# ArduinoRadioV3.net
KiCad netlist of a schematic drawn in EAGLE
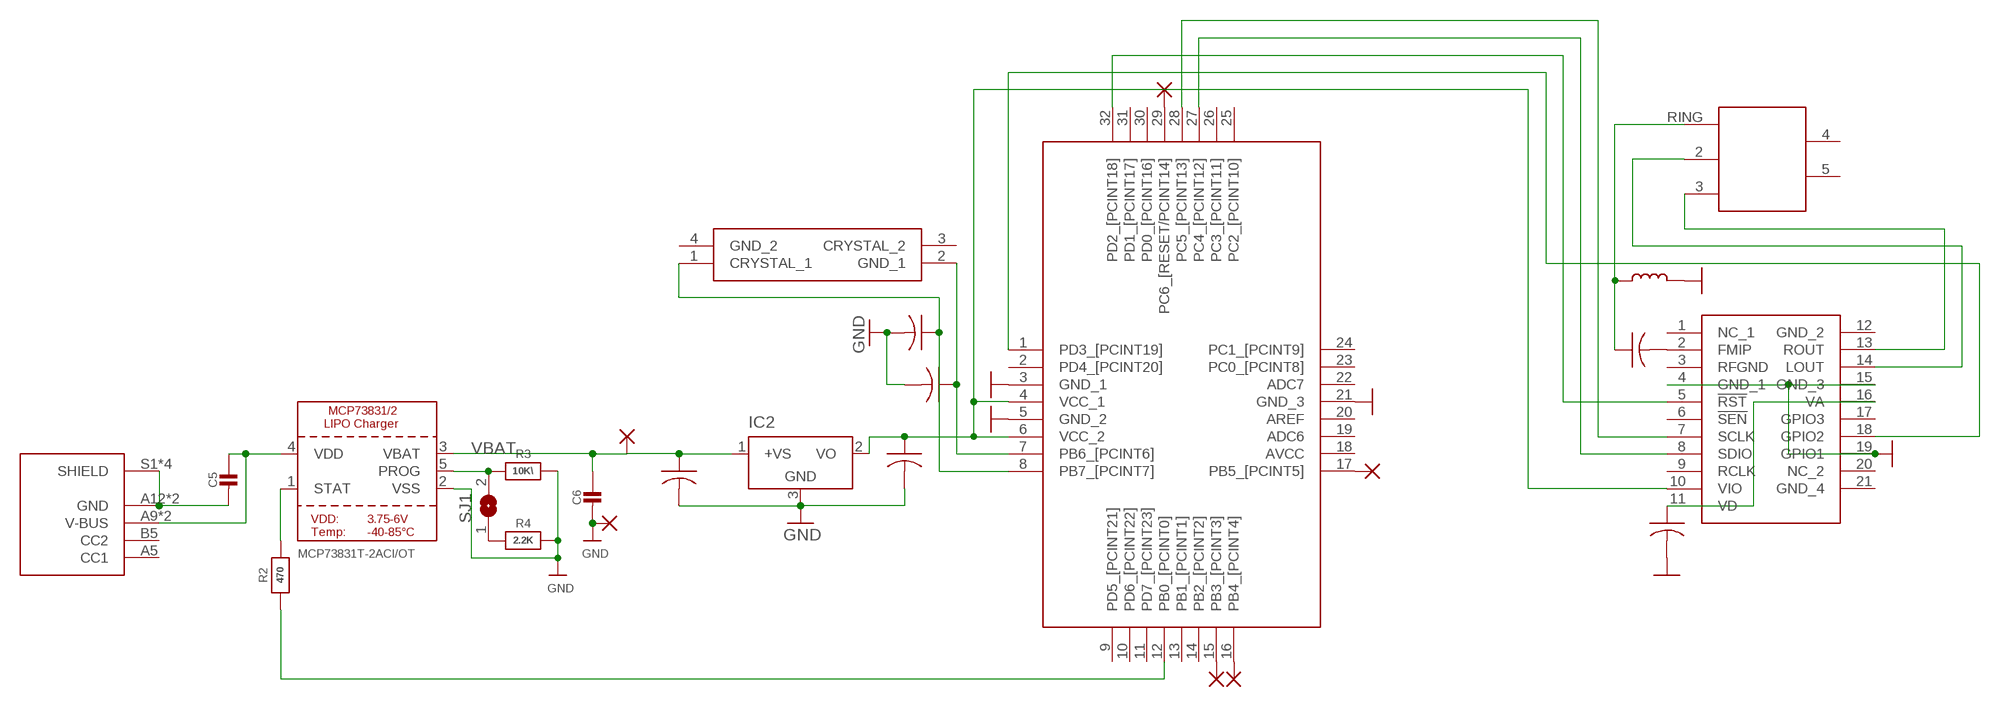
[diagram p0: schematic, sheet 1]

(export (version "E")
  (design (tool "Eeschema 10.0.6"))
  (components
    (comp (ref "C1")
      (value "10pF")
      (footprint "eagle-import:C0402")
      (libsource (lib "eagle-import") (part "rcl_334_C-USC0402"))
    )
    (comp (ref "C2")
      (value "10pF")
      (footprint "eagle-import:C0402")
      (libsource (lib "eagle-import") (part "rcl_334_C-USC0402"))
    )
    (comp (ref "C3")
      (value "47uf")
      (footprint "eagle-import:C1206")
      (libsource (lib "eagle-import") (part "better14pin_C-USC1206"))
    )
    (comp (ref "C4")
      (value "47uF")
      (footprint "eagle-import:C1206")
      (libsource (lib "eagle-import") (part "better14pin_C-USC1206"))
    )
    (comp (ref "C5")
      (value "10µF")
      (footprint "eagle-import:0805-NO@1")
      (libsource (lib "eagle-import") (part "CAP_CERAMIC0805-NOOUTLINE"))
    )
    (comp (ref "C6")
      (value "10µF")
      (footprint "eagle-import:0805-NO@1")
      (libsource (lib "eagle-import") (part "CAP_CERAMIC0805-NOOUTLINE"))
    )
    (comp (ref "C7")
      (value "22nF")
      (footprint "eagle-import:C0603")
      (libsource (lib "eagle-import") (part "C-USC0603"))
    )
    (comp (ref "C8")
      (value "100pF")
      (footprint "eagle-import:C1206")
      (libsource (lib "eagle-import") (part "C-USC1206"))
    )
    (comp (ref "IC1")
      (value "ATMEGA328P-AU")
      (footprint "eagle-import:QFP80P900X900X120-32N")
      (fields (field (name "MOUSER_PART_NUMBER") "556-ATMEGA328P-AU"))
      (libsource (lib "eagle-import") (part "ATMEGA328P-AU"))
    )
    (comp (ref "IC2")
      (value "LM50")
      (footprint "eagle-import:SOT23")
      (libsource (lib "eagle-import") (part "LM50"))
    )
    (comp (ref "IC3")
      (value "SI4703-C19-GM")
      (footprint "eagle-import:SI4703C19GM")
      (fields
        (field (name "MANUFACTURER_PART_NUMBER") "Si4703-C19-GM")
        (field (name "MOUSER_PART_NUMBER") "634-SI4703-C19-GM")
      )
      (libsource (lib "eagle-import") (part "SI4703-C19-GM"))
    )
    (comp (ref "J1")
      (value "UJC-HP-3-SMT-TR")
      (footprint "eagle-import:CUI_UJC-HP-3-SMT-TR")
      (fields (field (name "MF") "CUI Devices"))
      (libsource (lib "eagle-import") (part "UJC-HP-3-SMT-TR"))
    )
    (comp (ref "L1")
      (value "L_0603")
      (footprint "eagle-import:L0603")
      (libsource (lib "eagle-import") (part "L_0603"))
    )
    (comp (ref "PAD1")
      (value "WIREPADSMD1,27-254")
      (footprint "eagle-import:SMD1,27-2,54")
      (libsource (lib "eagle-import") (part "WIREPADSMD1,27-254"))
    )
    (comp (ref "PAD2")
      (value "WIREPADSMD1,27-254")
      (footprint "eagle-import:SMD1,27-2,54")
      (libsource (lib "eagle-import") (part "WIREPADSMD1,27-254"))
    )
    (comp (ref "PAD3")
      (value "SMD2")
      (footprint "eagle-import:SMD1,27-2,54")
      (libsource (lib "eagle-import") (part "SMD2"))
    )
    (comp (ref "PAD4")
      (value "SMD2")
      (footprint "eagle-import:SMD1,27-2,54")
      (libsource (lib "eagle-import") (part "SMD2"))
    )
    (comp (ref "PAD5")
      (value "SMD2")
      (footprint "eagle-import:SMD1,27-2,54")
      (libsource (lib "eagle-import") (part "SMD2"))
    )
    (comp (ref "PAD6")
      (value "SMD2")
      (footprint "eagle-import:SMD1,27-2,54")
      (libsource (lib "eagle-import") (part "SMD2"))
    )
    (comp (ref "R2")
      (value "470")
      (footprint "eagle-import:0603-NO")
      (libsource (lib "eagle-import") (part "RESISTOR_0603_NOOUT"))
    )
    (comp (ref "R3")
      (value "10K\\")
      (footprint "eagle-import:0603-NO")
      (libsource (lib "eagle-import") (part "RESISTOR_0603_NOOUT"))
    )
    (comp (ref "R4")
      (value "2.2K")
      (footprint "eagle-import:0603-NO")
      (libsource (lib "eagle-import") (part "RESISTOR_0603_NOOUT"))
    )
    (comp (ref "SJ1")
      (value "SOLDERJUMPER")
      (footprint "eagle-import:SOLDERJUMPER_ARROW_NOPASTE")
      (libsource (lib "eagle-import") (part "SOLDERJUMPER"))
    )
    (comp (ref "U$1")
      (value "STX-3542-5N-G-TR")
      (footprint "eagle-import:STX-3542-5N-G-TR")
      (libsource (lib "eagle-import") (part "STX-3542-5N-G-TR"))
    )
    (comp (ref "U1")
      (value "MCP73831T-2ACI/OT")
      (footprint "eagle-import:SOT23-5")
      (libsource (lib "eagle-import") (part "MCP73831/2"))
    )
    (comp (ref "Y1")
      (value "ABM3B-8.000MHZ-10-1-U-T")
      (footprint "eagle-import:ABM3B")
      (fields (field (name "MOUSER_PART_NUMBER") "815-ABM3B8MHZ101UT"))
      (libsource (lib "eagle-import") (part "ABM3B-8.000MHZ-10-1-U-T"))
    )
  )
  (nets
    (net (code "1") (name "/AVCC") (class "Default")
      (node (ref "IC1") (pin "18") (pinfunction "AVCC_18") (pintype "power_in"))
    )
    (net (code "2") (name "/STAT") (class "Default")
      (node (ref "IC1") (pin "12") (pinfunction "PB0_[PCINT0]_12") (pintype "bidirectional"))
      (node (ref "R2") (pin "1") (pinfunction "1_1") (pintype "passive"))
      (node (ref "R2") (pin "2") (pinfunction "2_2") (pintype "passive"))
      (node (ref "U1") (pin "1") (pinfunction "STAT_1") (pintype "output"))
    )
    (net (code "3") (name "/VBAT") (class "Default")
      (node (ref "C3") (pin "1") (pinfunction "1_1") (pintype "passive"))
      (node (ref "C6") (pin "1") (pinfunction "1_1") (pintype "passive"))
      (node (ref "C7") (pin "1") (pinfunction "1_1") (pintype "passive"))
      (node (ref "IC2") (pin "1") (pinfunction "+VS_1") (pintype "input"))
      (node (ref "IC3") (pin "11") (pinfunction "VD_11") (pintype "bidirectional"))
      (node (ref "IC3") (pin "16") (pinfunction "VA_16") (pintype "bidirectional"))
      (node (ref "PAD1") (pin "1") (pinfunction "P_1") (pintype "passive"))
      (node (ref "U1") (pin "3") (pinfunction "VBAT_3") (pintype "power_in"))
    )
    (net (code "4") (name "GND") (class "Default")
      (node (ref "C1") (pin "2") (pinfunction "2_2") (pintype "passive"))
      (node (ref "C2") (pin "2") (pinfunction "2_2") (pintype "passive"))
      (node (ref "C3") (pin "2") (pinfunction "2_2") (pintype "passive"))
      (node (ref "C4") (pin "2") (pinfunction "2_2") (pintype "passive"))
      (node (ref "C5") (pin "2") (pinfunction "2_2") (pintype "passive"))
      (node (ref "C6") (pin "2") (pinfunction "2_2") (pintype "passive"))
      (node (ref "C7") (pin "2") (pinfunction "2_2") (pintype "passive"))
      (node (ref "IC1") (pin "21") (pinfunction "GND_3_21") (pintype "power_in"))
      (node (ref "IC1") (pin "3") (pinfunction "GND_1_3") (pintype "power_in"))
      (node (ref "IC1") (pin "5") (pinfunction "GND_2_5") (pintype "power_in"))
      (node (ref "IC2") (pin "3") (pinfunction "GND_3") (pintype "power_in"))
      (node (ref "IC3") (pin "15") (pinfunction "GND_3_15") (pintype "bidirectional"))
      (node (ref "IC3") (pin "19") (pinfunction "GPIO1_19") (pintype "bidirectional"))
      (node (ref "IC3") (pin "4") (pinfunction "GND_1_4") (pintype "bidirectional"))
      (node (ref "J1") (pin "A12") (pinfunction "GND_A12") (pintype "power_in"))
      (node (ref "J1") (pin "B12") (pinfunction "GND_B12") (pintype "power_in"))
      (node (ref "J1") (pin "S1") (pinfunction "SHIELD_S1") (pintype "passive"))
      (node (ref "J1") (pin "S2") (pinfunction "SHIELD_S2") (pintype "passive"))
      (node (ref "J1") (pin "S3") (pinfunction "SHIELD_S3") (pintype "passive"))
      (node (ref "J1") (pin "S4") (pinfunction "SHIELD_S4") (pintype "passive"))
      (node (ref "L1") (pin "1") (pinfunction "1_1") (pintype "passive"))
      (node (ref "PAD2") (pin "1") (pinfunction "P_1") (pintype "passive"))
      (node (ref "R3") (pin "2") (pinfunction "2_2") (pintype "passive"))
      (node (ref "R4") (pin "2") (pinfunction "2_2") (pintype "passive"))
      (node (ref "U1") (pin "2") (pinfunction "VSS_2") (pintype "power_in"))
    )
    (net (code "5") (name "Net-(C8-Pad1)") (class "Default")
      (node (ref "C8") (pin "1") (pinfunction "1_1") (pintype "passive"))
      (node (ref "L1") (pin "2") (pinfunction "2_2") (pintype "passive"))
      (node (ref "U$1") (pin "RING") (pinfunction "RING_RING") (pintype "bidirectional"))
    )
    (net (code "6") (name "Net-(IC1-PB3_[PCINT3])") (class "Default")
      (node (ref "IC1") (pin "15") (pinfunction "PB3_[PCINT3]_15") (pintype "bidirectional"))
      (node (ref "PAD6") (pin "1") (pinfunction "P_1") (pintype "passive"))
    )
    (net (code "7") (name "Net-(IC1-PB4_[PCINT4])") (class "Default")
      (node (ref "IC1") (pin "16") (pinfunction "PB4_[PCINT4]_16") (pintype "bidirectional"))
      (node (ref "PAD5") (pin "1") (pinfunction "P_1") (pintype "passive"))
    )
    (net (code "8") (name "Net-(IC1-PB5_[PCINT5])") (class "Default")
      (node (ref "IC1") (pin "17") (pinfunction "PB5_[PCINT5]_17") (pintype "bidirectional"))
      (node (ref "PAD4") (pin "1") (pinfunction "P_1") (pintype "passive"))
    )
    (net (code "9") (name "Net-(IC1-PB6_[PCINT6])") (class "Default")
      (node (ref "C1") (pin "1") (pinfunction "1_1") (pintype "passive"))
      (node (ref "IC1") (pin "7") (pinfunction "PB6_[PCINT6]_7") (pintype "bidirectional"))
      (node (ref "Y1") (pin "2") (pinfunction "GND_1_2") (pintype "bidirectional"))
    )
    (net (code "10") (name "Net-(IC1-PB7_[PCINT7])") (class "Default")
      (node (ref "C2") (pin "1") (pinfunction "1_1") (pintype "passive"))
      (node (ref "IC1") (pin "8") (pinfunction "PB7_[PCINT7]_8") (pintype "bidirectional"))
      (node (ref "Y1") (pin "1") (pinfunction "CRYSTAL_1_1") (pintype "bidirectional"))
    )
    (net (code "11") (name "Net-(IC1-PC4_[PCINT12])") (class "Default")
      (node (ref "IC1") (pin "27") (pinfunction "PC4_[PCINT12]_27") (pintype "bidirectional"))
      (node (ref "IC3") (pin "8") (pinfunction "SDIO_8") (pintype "bidirectional"))
    )
    (net (code "12") (name "Net-(IC1-PC5_[PCINT13])") (class "Default")
      (node (ref "IC1") (pin "28") (pinfunction "PC5_[PCINT13]_28") (pintype "bidirectional"))
      (node (ref "IC3") (pin "7") (pinfunction "SCLK_7") (pintype "bidirectional"))
    )
    (net (code "13") (name "Net-(IC1-PC6_[RESET{slash}PCINT14])") (class "Default")
      (node (ref "IC1") (pin "29") (pinfunction "PC6_[RESET/PCINT14]_29") (pintype "bidirectional"))
      (node (ref "PAD3") (pin "1") (pinfunction "P_1") (pintype "passive"))
    )
    (net (code "14") (name "Net-(IC1-PD2_[PCINT18])") (class "Default")
      (node (ref "IC1") (pin "32") (pinfunction "PD2_[PCINT18]_32") (pintype "bidirectional"))
      (node (ref "IC3") (pin "5") (pinfunction "~{RST}_5") (pintype "bidirectional"))
    )
    (net (code "15") (name "Net-(IC1-PD3_[PCINT19])") (class "Default")
      (node (ref "IC1") (pin "1") (pinfunction "PD3_[PCINT19]_1") (pintype "bidirectional"))
      (node (ref "IC3") (pin "18") (pinfunction "GPIO2_18") (pintype "bidirectional"))
    )
    (net (code "16") (name "Net-(IC1-VCC_1)") (class "Default")
      (node (ref "C4") (pin "1") (pinfunction "1_1") (pintype "passive"))
      (node (ref "IC1") (pin "4") (pinfunction "VCC_1_4") (pintype "power_in"))
      (node (ref "IC1") (pin "6") (pinfunction "VCC_2_6") (pintype "power_in"))
      (node (ref "IC2") (pin "2") (pinfunction "VO_2") (pintype "input"))
      (node (ref "IC3") (pin "10") (pinfunction "VIO_10") (pintype "bidirectional"))
    )
    (net (code "17") (name "Net-(IC3-FMIP)") (class "Default")
      (node (ref "C8") (pin "2") (pinfunction "2_2") (pintype "passive"))
      (node (ref "IC3") (pin "2") (pinfunction "FMIP_2") (pintype "bidirectional"))
    )
    (net (code "18") (name "Net-(IC3-LOUT)") (class "Default")
      (node (ref "IC3") (pin "14") (pinfunction "LOUT_14") (pintype "bidirectional"))
      (node (ref "U$1") (pin "2") (pinfunction "2_2") (pintype "bidirectional"))
    )
    (net (code "19") (name "Net-(IC3-ROUT)") (class "Default")
      (node (ref "IC3") (pin "13") (pinfunction "ROUT_13") (pintype "bidirectional"))
      (node (ref "U$1") (pin "3") (pinfunction "3_3") (pintype "bidirectional"))
    )
    (net (code "20") (name "Net-(R4-Pad1)") (class "Default")
      (node (ref "R4") (pin "1") (pinfunction "1_1") (pintype "passive"))
      (node (ref "SJ1") (pin "1") (pinfunction "1_1") (pintype "passive"))
    )
    (net (code "21") (name "Net-(U1-PROG)") (class "Default")
      (node (ref "R3") (pin "1") (pinfunction "1_1") (pintype "passive"))
      (node (ref "SJ1") (pin "2") (pinfunction "2_2") (pintype "passive"))
      (node (ref "U1") (pin "5") (pinfunction "PROG_5") (pintype "input"))
    )
    (net (code "22") (name "Net-(U1-VDD)") (class "Default")
      (node (ref "C5") (pin "1") (pinfunction "1_1") (pintype "passive"))
      (node (ref "J1") (pin "A9") (pinfunction "V-BUS_A9") (pintype "power_in"))
      (node (ref "J1") (pin "B9") (pinfunction "V-BUS_B9") (pintype "power_in"))
      (node (ref "U1") (pin "4") (pinfunction "VDD_4") (pintype "power_in"))
    )
    (net (code "23") (name "unconnected-(IC1-ADC6-Pad19)") (class "Default")
      (node (ref "IC1") (pin "19") (pinfunction "ADC6_19") (pintype "bidirectional"))
    )
    (net (code "24") (name "unconnected-(IC1-ADC7-Pad22)") (class "Default")
      (node (ref "IC1") (pin "22") (pinfunction "ADC7_22") (pintype "bidirectional"))
    )
    (net (code "25") (name "unconnected-(IC1-AREF-Pad20)") (class "Default")
      (node (ref "IC1") (pin "20") (pinfunction "AREF_20") (pintype "bidirectional"))
    )
    (net (code "26") (name "unconnected-(IC1-PB1_[PCINT1]-Pad13)") (class "Default")
      (node (ref "IC1") (pin "13") (pinfunction "PB1_[PCINT1]_13") (pintype "bidirectional"))
    )
    (net (code "27") (name "unconnected-(IC1-PB2_[PCINT2]-Pad14)") (class "Default")
      (node (ref "IC1") (pin "14") (pinfunction "PB2_[PCINT2]_14") (pintype "bidirectional"))
    )
    (net (code "28") (name "unconnected-(IC1-PC0_[PCINT8]-Pad23)") (class "Default")
      (node (ref "IC1") (pin "23") (pinfunction "PC0_[PCINT8]_23") (pintype "bidirectional"))
    )
    (net (code "29") (name "unconnected-(IC1-PC1_[PCINT9]-Pad24)") (class "Default")
      (node (ref "IC1") (pin "24") (pinfunction "PC1_[PCINT9]_24") (pintype "bidirectional"))
    )
    (net (code "30") (name "unconnected-(IC1-PC2_[PCINT10]-Pad25)") (class "Default")
      (node (ref "IC1") (pin "25") (pinfunction "PC2_[PCINT10]_25") (pintype "bidirectional"))
    )
    (net (code "31") (name "unconnected-(IC1-PC3_[PCINT11]-Pad26)") (class "Default")
      (node (ref "IC1") (pin "26") (pinfunction "PC3_[PCINT11]_26") (pintype "bidirectional"))
    )
    (net (code "32") (name "unconnected-(IC1-PD0_[PCINT16]-Pad30)") (class "Default")
      (node (ref "IC1") (pin "30") (pinfunction "PD0_[PCINT16]_30") (pintype "bidirectional"))
    )
    (net (code "33") (name "unconnected-(IC1-PD1_[PCINT17]-Pad31)") (class "Default")
      (node (ref "IC1") (pin "31") (pinfunction "PD1_[PCINT17]_31") (pintype "bidirectional"))
    )
    (net (code "34") (name "unconnected-(IC1-PD4_[PCINT20]-Pad2)") (class "Default")
      (node (ref "IC1") (pin "2") (pinfunction "PD4_[PCINT20]_2") (pintype "bidirectional"))
    )
    (net (code "35") (name "unconnected-(IC1-PD5_[PCINT21]-Pad9)") (class "Default")
      (node (ref "IC1") (pin "9") (pinfunction "PD5_[PCINT21]_9") (pintype "bidirectional"))
    )
    (net (code "36") (name "unconnected-(IC1-PD6_[PCINT22]-Pad10)") (class "Default")
      (node (ref "IC1") (pin "10") (pinfunction "PD6_[PCINT22]_10") (pintype "bidirectional"))
    )
    (net (code "37") (name "unconnected-(IC1-PD7_[PCINT23]-Pad11)") (class "Default")
      (node (ref "IC1") (pin "11") (pinfunction "PD7_[PCINT23]_11") (pintype "bidirectional"))
    )
    (net (code "38") (name "unconnected-(IC3-GND_2-Pad12)") (class "Default")
      (node (ref "IC3") (pin "12") (pinfunction "GND_2_12") (pintype "bidirectional"))
    )
    (net (code "39") (name "unconnected-(IC3-GND_4-Pad21)") (class "Default")
      (node (ref "IC3") (pin "21") (pinfunction "GND_4_21") (pintype "bidirectional"))
    )
    (net (code "40") (name "unconnected-(IC3-GPIO3-Pad17)") (class "Default")
      (node (ref "IC3") (pin "17") (pinfunction "GPIO3_17") (pintype "bidirectional"))
    )
    (net (code "41") (name "unconnected-(IC3-NC_1-Pad1)") (class "Default")
      (node (ref "IC3") (pin "1") (pinfunction "NC_1_1") (pintype "bidirectional"))
    )
    (net (code "42") (name "unconnected-(IC3-NC_2-Pad20)") (class "Default")
      (node (ref "IC3") (pin "20") (pinfunction "NC_2_20") (pintype "bidirectional"))
    )
    (net (code "43") (name "unconnected-(IC3-RCLK-Pad9)") (class "Default")
      (node (ref "IC3") (pin "9") (pinfunction "RCLK_9") (pintype "bidirectional"))
    )
    (net (code "44") (name "unconnected-(IC3-RFGND-Pad3)") (class "Default")
      (node (ref "IC3") (pin "3") (pinfunction "RFGND_3") (pintype "bidirectional"))
    )
    (net (code "45") (name "unconnected-(IC3-~{SEN}-Pad6)") (class "Default")
      (node (ref "IC3") (pin "6") (pinfunction "~{SEN}_6") (pintype "bidirectional"))
    )
    (net (code "46") (name "unconnected-(J1-CC1-PadA5)") (class "Default")
      (node (ref "J1") (pin "A5") (pinfunction "CC1_A5") (pintype "bidirectional"))
    )
    (net (code "47") (name "unconnected-(J1-CC2-PadB5)") (class "Default")
      (node (ref "J1") (pin "B5") (pinfunction "CC2_B5") (pintype "bidirectional"))
    )
    (net (code "48") (name "unconnected-(U$1-Pad4)") (class "Default")
      (node (ref "U$1") (pin "4") (pinfunction "4_4") (pintype "bidirectional"))
    )
    (net (code "49") (name "unconnected-(U$1-Pad5)") (class "Default")
      (node (ref "U$1") (pin "5") (pinfunction "5_5") (pintype "bidirectional"))
    )
    (net (code "50") (name "unconnected-(Y1-CRYSTAL_2-Pad3)") (class "Default")
      (node (ref "Y1") (pin "3") (pinfunction "CRYSTAL_2_3") (pintype "bidirectional"))
    )
    (net (code "51") (name "unconnected-(Y1-GND_2-Pad4)") (class "Default")
      (node (ref "Y1") (pin "4") (pinfunction "GND_2_4") (pintype "bidirectional"))
    )
  )
)
